# TEMP.net
KiCad netlist of a schematic drawn in Altium Designer
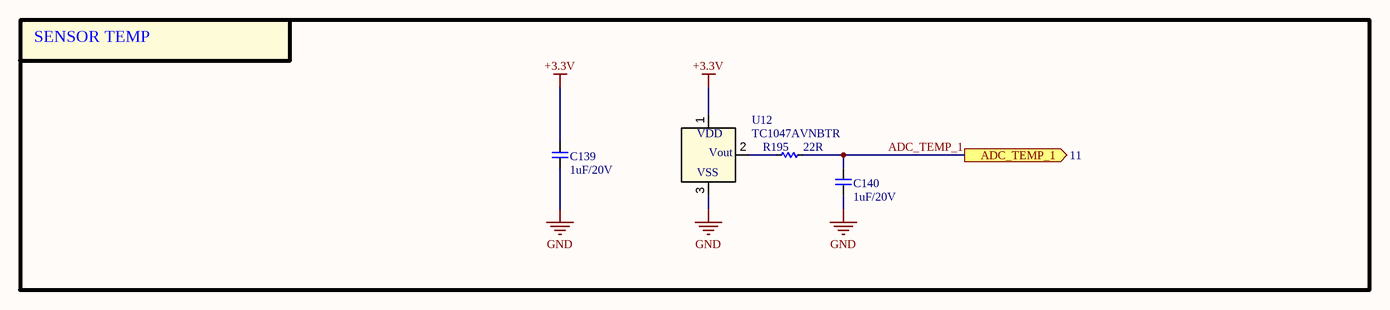
[diagram p0: TEMP.SchDoc]

(export (version "E")
  (design (tool "Eeschema 10.0.6"))
  (components
    (comp (ref "C139")
      (value "1uF/20V")
      (footprint "CAP_C_1005X50_L")
      (description "CAP CHIP")
      (libsource (lib "IFBschelib") (part "_CAP_C_2"))
    )
    (comp (ref "C140")
      (value "1uF/20V")
      (footprint "CAP_C_1005X50_L")
      (description "CAP CHIP")
      (libsource (lib "IFBschelib") (part "_CAP_C_2"))
    )
    (comp (ref "R195")
      (value "22R")
      (footprint "RES_C_1005x30_L")
      (description "RES")
      (libsource (lib "LABLIB") (part "_RES_B_2"))
    )
    (comp (ref "U12")
      (value "TC1047AVNBTR")
      (footprint "SOT-23_MC_MCH")
      (description "SENSOR ANALOG -40C-125C SOT23-3")
      (fields (field (name "COPYRIGHT") "Copyright (C) 2025 Ultra Librarian. All rights reserved."))
      (libsource (lib "IFBschelib") (part "TC1047AVNBTR"))
    )
  )
  (nets
    (net (code "1") (name "+3.3V") (class "Default")
      (node (ref "C139") (pin "2") (pinfunction "2_2") (pintype "passive"))
      (node (ref "U12") (pin "1") (pinfunction "VDD_1") (pintype "passive"))
    )
    (net (code "2") (name "/ADC_TEMP_1") (class "Default")
      (node (ref "C140") (pin "2") (pinfunction "2_2") (pintype "passive"))
      (node (ref "R195") (pin "2") (pinfunction "2_2") (pintype "passive"))
    )
    (net (code "3") (name "GND") (class "Default")
      (node (ref "C139") (pin "1") (pinfunction "1_1") (pintype "passive"))
      (node (ref "C140") (pin "1") (pinfunction "1_1") (pintype "passive"))
      (node (ref "U12") (pin "3") (pinfunction "VSS_3") (pintype "passive"))
    )
    (net (code "4") (name "Net-(U12-VOUT)") (class "Default")
      (node (ref "R195") (pin "1") (pinfunction "1_1") (pintype "passive"))
      (node (ref "U12") (pin "2") (pinfunction "VOUT_2") (pintype "passive"))
    )
  )
)
